# can_uart.net
KiCad netlist of a schematic drawn in Altium Designer
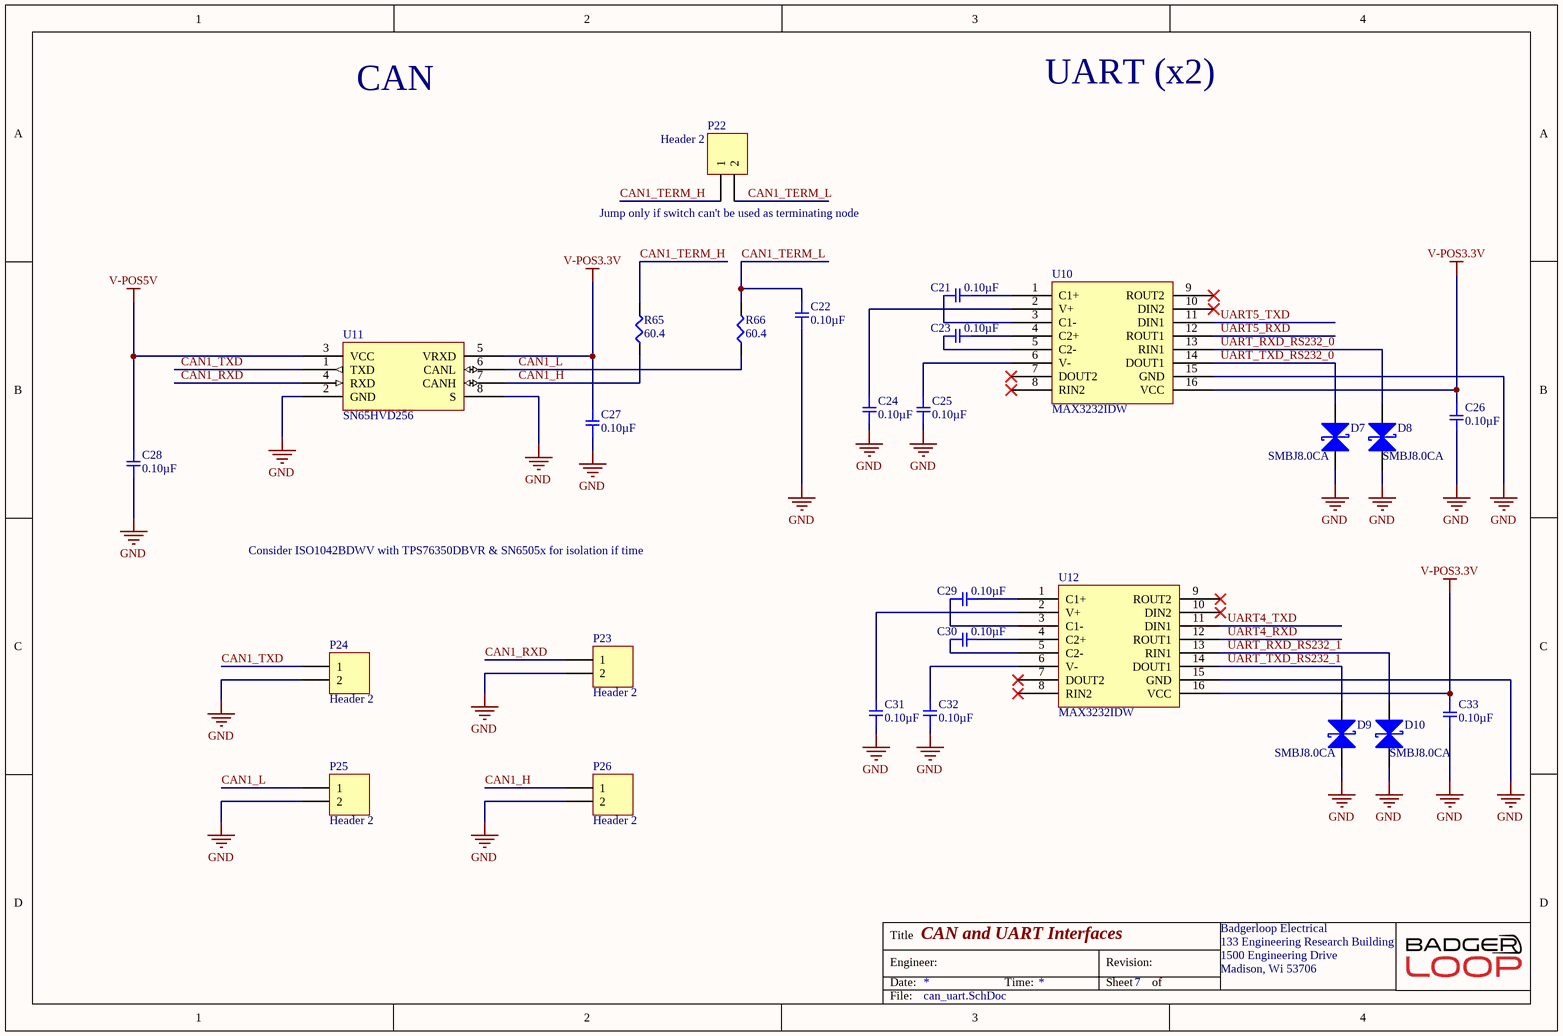
[diagram p0: can_uart.SchDoc]

(export (version "E")
  (design (tool "Eeschema 10.0.6"))
  (components
    (comp (ref "C21")
      (value "0.10µF")
      (footprint "SMD-0805C")
      (description "CAP CER 0.1UF 16V X7R 0805")
      (fields
        (field (name "DIGI-KEY PART NUMBER") "490-12557-1-ND")
        (field (name "PART NUMBER") "GRM219R71C104JA01D")
      )
      (libsource (lib "capacitors") (part "GRM219R71C104JA01D"))
    )
    (comp (ref "C22")
      (value "0.10µF")
      (footprint "SMD-0805C")
      (description "CAP CER 0.1UF 16V X7R 0805")
      (fields
        (field (name "DIGI-KEY PART NUMBER") "490-12557-1-ND")
        (field (name "PART NUMBER") "GRM219R71C104JA01D")
      )
      (libsource (lib "capacitors") (part "GRM219R71C104JA01D"))
    )
    (comp (ref "C23")
      (value "0.10µF")
      (footprint "SMD-0805C")
      (description "CAP CER 0.1UF 16V X7R 0805")
      (fields
        (field (name "DIGI-KEY PART NUMBER") "490-12557-1-ND")
        (field (name "PART NUMBER") "GRM219R71C104JA01D")
      )
      (libsource (lib "capacitors") (part "GRM219R71C104JA01D"))
    )
    (comp (ref "C24")
      (value "0.10µF")
      (footprint "SMD-0805C")
      (description "CAP CER 0.1UF 16V X7R 0805")
      (fields
        (field (name "DIGI-KEY PART NUMBER") "490-12557-1-ND")
        (field (name "PART NUMBER") "GRM219R71C104JA01D")
      )
      (libsource (lib "capacitors") (part "GRM219R71C104JA01D"))
    )
    (comp (ref "C25")
      (value "0.10µF")
      (footprint "SMD-0805C")
      (description "CAP CER 0.1UF 16V X7R 0805")
      (fields
        (field (name "DIGI-KEY PART NUMBER") "490-12557-1-ND")
        (field (name "PART NUMBER") "GRM219R71C104JA01D")
      )
      (libsource (lib "capacitors") (part "GRM219R71C104JA01D"))
    )
    (comp (ref "C26")
      (value "0.10µF")
      (footprint "SMD-0805C")
      (description "CAP CER 0.1UF 25V X7R 0805")
      (fields
        (field (name "DIGI-KEY PART NUMBER") "490-12754-1-ND")
        (field (name "PART NUMBER") "GRM219R71E104KA01D")
      )
      (libsource (lib "capacitors") (part "GRM219R71E104KA01D"))
    )
    (comp (ref "C27")
      (value "0.10µF")
      (footprint "SMD-0805C")
      (description "CAP CER 0.1UF 16V X7R 0805")
      (fields
        (field (name "DIGI-KEY PART NUMBER") "490-12557-1-ND")
        (field (name "PART NUMBER") "GRM219R71C104JA01D")
      )
      (libsource (lib "capacitors") (part "GRM219R71C104JA01D"))
    )
    (comp (ref "C28")
      (value "0.10µF")
      (footprint "SMD-0805C")
      (description "CAP CER 0.1UF 16V X7R 0805")
      (fields
        (field (name "DIGI-KEY PART NUMBER") "490-12557-1-ND")
        (field (name "PART NUMBER") "GRM219R71C104JA01D")
      )
      (libsource (lib "capacitors") (part "GRM219R71C104JA01D"))
    )
    (comp (ref "C29")
      (value "0.10µF")
      (footprint "SMD-0805C")
      (description "CAP CER 0.1UF 16V X7R 0805")
      (fields
        (field (name "DIGI-KEY PART NUMBER") "490-12557-1-ND")
        (field (name "PART NUMBER") "GRM219R71C104JA01D")
      )
      (libsource (lib "capacitors") (part "GRM219R71C104JA01D"))
    )
    (comp (ref "C30")
      (value "0.10µF")
      (footprint "SMD-0805C")
      (description "CAP CER 0.1UF 16V X7R 0805")
      (fields
        (field (name "DIGI-KEY PART NUMBER") "490-12557-1-ND")
        (field (name "PART NUMBER") "GRM219R71C104JA01D")
      )
      (libsource (lib "capacitors") (part "GRM219R71C104JA01D"))
    )
    (comp (ref "C31")
      (value "0.10µF")
      (footprint "SMD-0805C")
      (description "CAP CER 0.1UF 16V X7R 0805")
      (fields
        (field (name "DIGI-KEY PART NUMBER") "490-12557-1-ND")
        (field (name "PART NUMBER") "GRM219R71C104JA01D")
      )
      (libsource (lib "capacitors") (part "GRM219R71C104JA01D"))
    )
    (comp (ref "C32")
      (value "0.10µF")
      (footprint "SMD-0805C")
      (description "CAP CER 0.1UF 16V X7R 0805")
      (fields
        (field (name "DIGI-KEY PART NUMBER") "490-12557-1-ND")
        (field (name "PART NUMBER") "GRM219R71C104JA01D")
      )
      (libsource (lib "capacitors") (part "GRM219R71C104JA01D"))
    )
    (comp (ref "C33")
      (value "0.10µF")
      (footprint "SMD-0805C")
      (description "CAP CER 0.1UF 25V X7R 0805")
      (fields
        (field (name "DIGI-KEY PART NUMBER") "490-12754-1-ND")
        (field (name "PART NUMBER") "GRM219R71E104KA01D")
      )
      (libsource (lib "capacitors") (part "GRM219R71E104KA01D"))
    )
    (comp (ref "D7")
      (value "SMBJ8.0CA")
      (footprint "DIOM4436X26N")
      (description "TVS DIODE 8V 13.6V DO214AA")
      (fields (field (name "MANUFACTURER") "Littelfuse"))
      (libsource (lib "misc") (part "SMBJ8.0CA"))
    )
    (comp (ref "D8")
      (value "SMBJ8.0CA")
      (footprint "DIOM4436X26N")
      (description "TVS DIODE 8V 13.6V DO214AA")
      (fields (field (name "MANUFACTURER") "Littelfuse"))
      (libsource (lib "misc") (part "SMBJ8.0CA"))
    )
    (comp (ref "D9")
      (value "SMBJ8.0CA")
      (footprint "DIOM4436X26N")
      (description "TVS DIODE 8V 13.6V DO214AA")
      (fields (field (name "MANUFACTURER") "Littelfuse"))
      (libsource (lib "misc") (part "SMBJ8.0CA"))
    )
    (comp (ref "D10")
      (value "SMBJ8.0CA")
      (footprint "DIOM4436X26N")
      (description "TVS DIODE 8V 13.6V DO214AA")
      (fields (field (name "MANUFACTURER") "Littelfuse"))
      (libsource (lib "misc") (part "SMBJ8.0CA"))
    )
    (comp (ref "P22")
      (value "Header 2")
      (footprint "Pin Header 1x2 TH Pitch 2.54mm")
      (description "Header, 2-Pin")
      (fields (field (name "PUBLISHER") "Altium Limited"))
      (libsource (lib "") (part "Header 2_1"))
    )
    (comp (ref "P23")
      (value "Header 2")
      (footprint "Pin Header 1x2 TH Pitch 2.54mm")
      (description "Header, 2-Pin")
      (fields (field (name "PUBLISHER") "Altium Limited"))
      (libsource (lib "connector") (part "Header 2"))
    )
    (comp (ref "P24")
      (value "Header 2")
      (footprint "Pin Header 1x2 TH Pitch 2.54mm")
      (description "Header, 2-Pin")
      (fields (field (name "PUBLISHER") "Altium Limited"))
      (libsource (lib "connector") (part "Header 2"))
    )
    (comp (ref "P25")
      (value "Header 2")
      (footprint "Pin Header 1x2 TH Pitch 2.54mm")
      (description "Header, 2-Pin")
      (fields (field (name "PUBLISHER") "Altium Limited"))
      (libsource (lib "connector") (part "Header 2"))
    )
    (comp (ref "P26")
      (value "Header 2")
      (footprint "Pin Header 1x2 TH Pitch 2.54mm")
      (description "Header, 2-Pin")
      (fields (field (name "PUBLISHER") "Altium Limited"))
      (libsource (lib "connector") (part "Header 2"))
    )
    (comp (ref "R65")
      (value "60.4")
      (footprint "SMD-1206-RES")
      (description "RES SMD 60.4 OHM 1% 1/4W 1206")
      (fields
        (field (name "PART NUMBER") "ERJ-8ENF60R4V")
        (field (name "DIGI-KEY PART NUMBER") "P60.4FCT-ND")
      )
      (libsource (lib "resistors") (part "ERJ-8ENF60R4V"))
    )
    (comp (ref "R66")
      (value "60.4")
      (footprint "SMD-1206-RES")
      (description "RES SMD 60.4 OHM 1% 1/4W 1206")
      (fields
        (field (name "PART NUMBER") "ERJ-8ENF60R4V")
        (field (name "DIGI-KEY PART NUMBER") "P60.4FCT-ND")
      )
      (libsource (lib "resistors") (part "ERJ-8ENF60R4V"))
    )
    (comp (ref "U10")
      (value "MAX3232IDW")
      (footprint "SOP127P1060X175-16N")
      (description "IC DRVR/RCVR MULTCH RS232 16SOIC")
      (fields (field (name "MANUFACTURER") "Texas Instruments"))
      (libsource (lib "ic") (part "MAX3232IDW"))
    )
    (comp (ref "U11")
      (value "SN65HVD256")
      (footprint "SOIC127P610X280-8N")
      (description "IC TXRX CAN 5V HS 8SOIC")
      (fields (field (name "MANUFACTURER") "TI"))
      (libsource (lib "ic") (part "SN65HVD256"))
    )
    (comp (ref "U12")
      (value "MAX3232IDW")
      (footprint "SOP127P1060X175-16N")
      (description "IC DRVR/RCVR MULTCH RS232 16SOIC")
      (fields (field (name "MANUFACTURER") "Texas Instruments"))
      (libsource (lib "ic") (part "MAX3232IDW"))
    )
  )
  (nets
    (net (code "1") (name "/CAN1_H") (class "Default")
      (node (ref "P26") (pin "1") (pinfunction "1_1") (pintype "passive"))
      (node (ref "R65") (pin "1") (pinfunction "1_1") (pintype "passive"))
      (node (ref "U11") (pin "7") (pinfunction "CANH_7") (pintype "bidirectional"))
    )
    (net (code "2") (name "/CAN1_L") (class "Default")
      (node (ref "P25") (pin "1") (pinfunction "1_1") (pintype "passive"))
      (node (ref "R66") (pin "1") (pinfunction "1_1") (pintype "passive"))
      (node (ref "U11") (pin "6") (pinfunction "CANL_6") (pintype "bidirectional"))
    )
    (net (code "3") (name "/CAN1_RXD") (class "Default")
      (node (ref "P23") (pin "1") (pinfunction "1_1") (pintype "passive"))
      (node (ref "U11") (pin "4") (pinfunction "RXD_4") (pintype "input"))
    )
    (net (code "4") (name "/CAN1_TERM_H") (class "Default")
      (node (ref "P22") (pin "1") (pinfunction "1_1") (pintype "passive"))
      (node (ref "R65") (pin "2") (pinfunction "2_2") (pintype "passive"))
    )
    (net (code "5") (name "/CAN1_TERM_L") (class "Default")
      (node (ref "C22") (pin "2") (pinfunction "2_2") (pintype "passive"))
      (node (ref "P22") (pin "2") (pinfunction "2_2") (pintype "passive"))
      (node (ref "R66") (pin "2") (pinfunction "2_2") (pintype "passive"))
    )
    (net (code "6") (name "/CAN1_TXD") (class "Default")
      (node (ref "P24") (pin "1") (pinfunction "1_1") (pintype "passive"))
      (node (ref "U11") (pin "1") (pinfunction "TXD_1") (pintype "output"))
    )
    (net (code "7") (name "/UART4_RXD") (class "Default")
      (node (ref "U12") (pin "12") (pinfunction "ROUT1_12") (pintype "passive"))
    )
    (net (code "8") (name "/UART4_TXD") (class "Default")
      (node (ref "U12") (pin "11") (pinfunction "DIN1_11") (pintype "passive"))
    )
    (net (code "9") (name "/UART5_RXD") (class "Default")
      (node (ref "U10") (pin "12") (pinfunction "ROUT1_12") (pintype "passive"))
    )
    (net (code "10") (name "/UART5_TXD") (class "Default")
      (node (ref "U10") (pin "11") (pinfunction "DIN1_11") (pintype "passive"))
    )
    (net (code "11") (name "/UART_RXD_RS232_0") (class "Default")
      (node (ref "D8") (pin "2") (pinfunction "K_2") (pintype "passive"))
      (node (ref "U10") (pin "13") (pinfunction "RIN1_13") (pintype "passive"))
    )
    (net (code "12") (name "/UART_RXD_RS232_1") (class "Default")
      (node (ref "D10") (pin "2") (pinfunction "K_2") (pintype "passive"))
      (node (ref "U12") (pin "13") (pinfunction "RIN1_13") (pintype "passive"))
    )
    (net (code "13") (name "/UART_TXD_RS232_0") (class "Default")
      (node (ref "D7") (pin "2") (pinfunction "K_2") (pintype "passive"))
      (node (ref "U10") (pin "14") (pinfunction "DOUT1_14") (pintype "passive"))
    )
    (net (code "14") (name "/UART_TXD_RS232_1") (class "Default")
      (node (ref "D9") (pin "2") (pinfunction "K_2") (pintype "passive"))
      (node (ref "U12") (pin "14") (pinfunction "DOUT1_14") (pintype "passive"))
    )
    (net (code "15") (name "GND") (class "Default")
      (node (ref "C22") (pin "1") (pinfunction "1_1") (pintype "passive"))
      (node (ref "C24") (pin "1") (pinfunction "1_1") (pintype "passive"))
      (node (ref "C25") (pin "1") (pinfunction "1_1") (pintype "passive"))
      (node (ref "C26") (pin "2") (pinfunction "2_2") (pintype "passive"))
      (node (ref "C27") (pin "1") (pinfunction "1_1") (pintype "passive"))
      (node (ref "C28") (pin "1") (pinfunction "1_1") (pintype "passive"))
      (node (ref "C31") (pin "1") (pinfunction "1_1") (pintype "passive"))
      (node (ref "C32") (pin "1") (pinfunction "1_1") (pintype "passive"))
      (node (ref "C33") (pin "2") (pinfunction "2_2") (pintype "passive"))
      (node (ref "D10") (pin "1") (pinfunction "A_1") (pintype "passive"))
      (node (ref "D7") (pin "1") (pinfunction "A_1") (pintype "passive"))
      (node (ref "D8") (pin "1") (pinfunction "A_1") (pintype "passive"))
      (node (ref "D9") (pin "1") (pinfunction "A_1") (pintype "passive"))
      (node (ref "P23") (pin "2") (pinfunction "2_2") (pintype "passive"))
      (node (ref "P24") (pin "2") (pinfunction "2_2") (pintype "passive"))
      (node (ref "P25") (pin "2") (pinfunction "2_2") (pintype "passive"))
      (node (ref "P26") (pin "2") (pinfunction "2_2") (pintype "passive"))
      (node (ref "U10") (pin "15") (pinfunction "GND_15") (pintype "passive"))
      (node (ref "U11") (pin "2") (pinfunction "GND_2") (pintype "power_in"))
      (node (ref "U11") (pin "8") (pinfunction "S_8") (pintype "passive"))
      (node (ref "U12") (pin "15") (pinfunction "GND_15") (pintype "passive"))
    )
    (net (code "16") (name "Net-(U10-C1+)") (class "Default")
      (node (ref "C21") (pin "2") (pinfunction "2_2") (pintype "passive"))
      (node (ref "U10") (pin "1") (pinfunction "C1+_1") (pintype "passive"))
    )
    (net (code "17") (name "Net-(U10-C1-)") (class "Default")
      (node (ref "C21") (pin "1") (pinfunction "1_1") (pintype "passive"))
      (node (ref "U10") (pin "3") (pinfunction "C1-_3") (pintype "passive"))
    )
    (net (code "18") (name "Net-(U10-C2+)") (class "Default")
      (node (ref "C23") (pin "2") (pinfunction "2_2") (pintype "passive"))
      (node (ref "U10") (pin "4") (pinfunction "C2+_4") (pintype "passive"))
    )
    (net (code "19") (name "Net-(U10-C2-)") (class "Default")
      (node (ref "C23") (pin "1") (pinfunction "1_1") (pintype "passive"))
      (node (ref "U10") (pin "5") (pinfunction "C2-_5") (pintype "passive"))
    )
    (net (code "20") (name "Net-(U10-V+)") (class "Default")
      (node (ref "C24") (pin "2") (pinfunction "2_2") (pintype "passive"))
      (node (ref "U10") (pin "2") (pinfunction "V+_2") (pintype "passive"))
    )
    (net (code "21") (name "Net-(U10-V-)") (class "Default")
      (node (ref "C25") (pin "2") (pinfunction "2_2") (pintype "passive"))
      (node (ref "U10") (pin "6") (pinfunction "V-_6") (pintype "passive"))
    )
    (net (code "22") (name "Net-(U12-C1+)") (class "Default")
      (node (ref "C29") (pin "2") (pinfunction "2_2") (pintype "passive"))
      (node (ref "U12") (pin "1") (pinfunction "C1+_1") (pintype "passive"))
    )
    (net (code "23") (name "Net-(U12-C1-)") (class "Default")
      (node (ref "C29") (pin "1") (pinfunction "1_1") (pintype "passive"))
      (node (ref "U12") (pin "3") (pinfunction "C1-_3") (pintype "passive"))
    )
    (net (code "24") (name "Net-(U12-C2+)") (class "Default")
      (node (ref "C30") (pin "2") (pinfunction "2_2") (pintype "passive"))
      (node (ref "U12") (pin "4") (pinfunction "C2+_4") (pintype "passive"))
    )
    (net (code "25") (name "Net-(U12-C2-)") (class "Default")
      (node (ref "C30") (pin "1") (pinfunction "1_1") (pintype "passive"))
      (node (ref "U12") (pin "5") (pinfunction "C2-_5") (pintype "passive"))
    )
    (net (code "26") (name "Net-(U12-V+)") (class "Default")
      (node (ref "C31") (pin "2") (pinfunction "2_2") (pintype "passive"))
      (node (ref "U12") (pin "2") (pinfunction "V+_2") (pintype "passive"))
    )
    (net (code "27") (name "Net-(U12-V-)") (class "Default")
      (node (ref "C32") (pin "2") (pinfunction "2_2") (pintype "passive"))
      (node (ref "U12") (pin "6") (pinfunction "V-_6") (pintype "passive"))
    )
    (net (code "28") (name "V-POS3.3V") (class "Default")
      (node (ref "C26") (pin "1") (pinfunction "1_1") (pintype "passive"))
      (node (ref "C27") (pin "2") (pinfunction "2_2") (pintype "passive"))
      (node (ref "C33") (pin "1") (pinfunction "1_1") (pintype "passive"))
      (node (ref "U10") (pin "16") (pinfunction "VCC_16") (pintype "passive"))
      (node (ref "U11") (pin "5") (pinfunction "VRXD_5") (pintype "power_in"))
      (node (ref "U12") (pin "16") (pinfunction "VCC_16") (pintype "passive"))
    )
    (net (code "29") (name "V-POS5V") (class "Default")
      (node (ref "C28") (pin "2") (pinfunction "2_2") (pintype "passive"))
      (node (ref "U11") (pin "3") (pinfunction "VCC_3") (pintype "power_in"))
    )
    (net (code "30") (name "unconnected-(U10-DIN2-Pad10)") (class "Default")
      (node (ref "U10") (pin "10") (pinfunction "DIN2_10") (pintype "passive+no_connect"))
    )
    (net (code "31") (name "unconnected-(U10-DOUT2-Pad7)") (class "Default")
      (node (ref "U10") (pin "7") (pinfunction "DOUT2_7") (pintype "passive+no_connect"))
    )
    (net (code "32") (name "unconnected-(U10-RIN2-Pad8)") (class "Default")
      (node (ref "U10") (pin "8") (pinfunction "RIN2_8") (pintype "passive+no_connect"))
    )
    (net (code "33") (name "unconnected-(U10-ROUT2-Pad9)") (class "Default")
      (node (ref "U10") (pin "9") (pinfunction "ROUT2_9") (pintype "passive+no_connect"))
    )
    (net (code "34") (name "unconnected-(U12-DIN2-Pad10)") (class "Default")
      (node (ref "U12") (pin "10") (pinfunction "DIN2_10") (pintype "passive+no_connect"))
    )
    (net (code "35") (name "unconnected-(U12-DOUT2-Pad7)") (class "Default")
      (node (ref "U12") (pin "7") (pinfunction "DOUT2_7") (pintype "passive+no_connect"))
    )
    (net (code "36") (name "unconnected-(U12-RIN2-Pad8)") (class "Default")
      (node (ref "U12") (pin "8") (pinfunction "RIN2_8") (pintype "passive+no_connect"))
    )
    (net (code "37") (name "unconnected-(U12-ROUT2-Pad9)") (class "Default")
      (node (ref "U12") (pin "9") (pinfunction "ROUT2_9") (pintype "passive+no_connect"))
    )
  )
)
